# Sheet2.net
KiCad netlist of a schematic drawn in Altium Designer
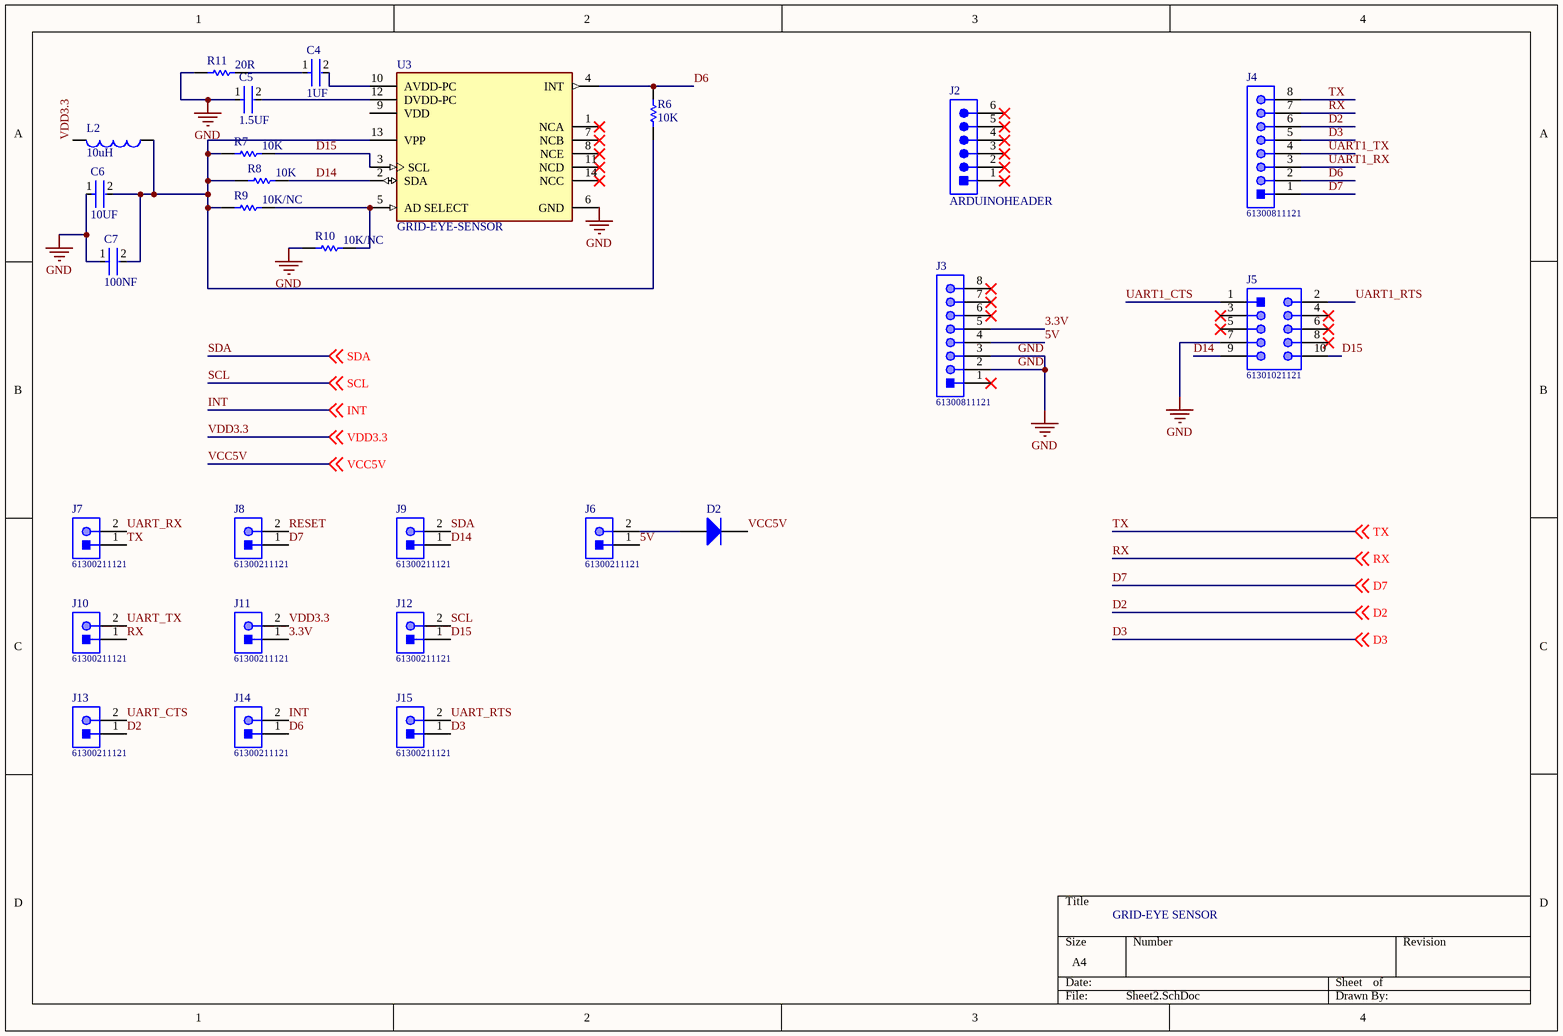
[diagram p0: Sheet2.SchDoc]

(export (version "E")
  (design (tool "Eeschema 10.0.6"))
  (components
    (comp (ref "C4")
      (value "1UF")
      (footprint "FP-C0805C-DN-MFG")
      (description "CAP CER 0.1UF 50V X7R 0805")
      (fields
        (field (name "MANUFACTURER PART NUMBER") "C0805C104K5RACTU")
        (field (name "MANUFACTURER") "KEMET")
      )
      (libsource (lib "Altium Content Vault") (part "b4654b650e69147ec39a6b967a45e02"))
    )
    (comp (ref "C5")
      (value "1.5UF")
      (footprint "FP-C0805C-DN-MFG")
      (description "CAP CER 0.1UF 50V X7R 0805")
      (fields
        (field (name "MANUFACTURER PART NUMBER") "C0805C104K5RACTU")
        (field (name "MANUFACTURER") "KEMET")
      )
      (libsource (lib "Altium Content Vault") (part "b4654b650e69147ec39a6b967a45e02"))
    )
    (comp (ref "C6")
      (value "10UF")
      (footprint "FP-C0805C-DN-MFG")
      (description "CAP CER 0.1UF 50V X7R 0805")
      (fields
        (field (name "MANUFACTURER PART NUMBER") "C0805C104K5RACTU")
        (field (name "MANUFACTURER") "KEMET")
      )
      (libsource (lib "Altium Content Vault") (part "b4654b650e69147ec39a6b967a45e02"))
    )
    (comp (ref "C7")
      (value "100NF")
      (footprint "FP-C0805C-DN-MFG")
      (description "CAP CER 0.1UF 50V X7R 0805")
      (fields
        (field (name "MANUFACTURER PART NUMBER") "C0805C104K5RACTU")
        (field (name "MANUFACTURER") "KEMET")
      )
      (libsource (lib "Altium Content Vault") (part "b4654b650e69147ec39a6b967a45e02"))
    )
    (comp (ref "D2")
      (value "1N4148W-7-F")
      (footprint "DIOD-SOD123-2_V")
      (description "Fast Switching Diode, 100 V, 0.15 A, -65 to 150 degC, 2-Pin?SOD123, RoHS, Tape and Reel")
      (fields (field (name "MANUFACTURER") "DiodesIncorporated"))
      (libsource (lib "Altium Content Vault") (part "D-AK-2"))
    )
    (comp (ref "J2")
      (value "ARDUINOHEADER")
      (footprint "TECO-640456-6_V")
      (fields (field (name "MANUFACTURER") "TE Connectivity"))
      (libsource (lib "Altium Content Vault") (part "CN-1P-M-R6"))
    )
    (comp (ref "J3")
      (value "61300811121")
      (footprint "61300811121")
      (description "THT Vertical Pin Header WR-PHD, Pitch 2.54 mm, Single Row, 8 pins")
      (fields (field (name "MANUFACTURER") "Wurth Elektronik") (field (name "PUBLISHER") "WurthElektronik"))
      (libsource (lib "Altium Content Vault") (part "WE-CN-1P-M-R8"))
    )
    (comp (ref "J4")
      (value "61300811121")
      (footprint "61300811121")
      (description "THT Vertical Pin Header WR-PHD, Pitch 2.54 mm, Single Row, 8 pins")
      (fields (field (name "MANUFACTURER") "Wurth Elektronik") (field (name "PUBLISHER") "WurthElektronik"))
      (libsource (lib "Altium Content Vault") (part "WE-CN-1P-M-R8"))
    )
    (comp (ref "J5")
      (value "61301021121")
      (footprint "61301021121")
      (description "THT Vertical Pin Header WR-PHD, Pitch 2.54 mm, Dual Row, 10 pins")
      (fields (field (name "MANUFACTURER") "Wurth Elektronik") (field (name "PUBLISHER") "WurthElektronik"))
      (libsource (lib "Altium Content Vault") (part "WE-CN-2P-M-R10"))
    )
    (comp (ref "J6")
      (value "61300211121")
      (footprint "61300211121")
      (description "THT Vertical Pin Header WR-PHD, Pitch 2.54 mm, Single Row, 2 pins")
      (fields (field (name "MANUFACTURER") "Wurth Elektronik") (field (name "PUBLISHER") "WurthElektronik"))
      (libsource (lib "Altium Content Vault") (part "WE-CN-1P-M-R2"))
    )
    (comp (ref "J7")
      (value "61300211121")
      (footprint "61300211121")
      (description "THT Vertical Pin Header WR-PHD, Pitch 2.54 mm, Single Row, 2 pins")
      (fields (field (name "MANUFACTURER") "Wurth Elektronik") (field (name "PUBLISHER") "WurthElektronik"))
      (libsource (lib "Altium Content Vault") (part "WE-CN-1P-M-R2"))
    )
    (comp (ref "J8")
      (value "61300211121")
      (footprint "61300211121")
      (description "THT Vertical Pin Header WR-PHD, Pitch 2.54 mm, Single Row, 2 pins")
      (fields (field (name "MANUFACTURER") "Wurth Elektronik") (field (name "PUBLISHER") "WurthElektronik"))
      (libsource (lib "Altium Content Vault") (part "WE-CN-1P-M-R2"))
    )
    (comp (ref "J9")
      (value "61300211121")
      (footprint "61300211121")
      (description "THT Vertical Pin Header WR-PHD, Pitch 2.54 mm, Single Row, 2 pins")
      (fields (field (name "MANUFACTURER") "Wurth Elektronik") (field (name "PUBLISHER") "WurthElektronik"))
      (libsource (lib "Altium Content Vault") (part "WE-CN-1P-M-R2"))
    )
    (comp (ref "J10")
      (value "61300211121")
      (footprint "61300211121")
      (description "THT Vertical Pin Header WR-PHD, Pitch 2.54 mm, Single Row, 2 pins")
      (fields (field (name "MANUFACTURER") "Wurth Elektronik") (field (name "PUBLISHER") "WurthElektronik"))
      (libsource (lib "Altium Content Vault") (part "WE-CN-1P-M-R2"))
    )
    (comp (ref "J11")
      (value "61300211121")
      (footprint "61300211121")
      (description "THT Vertical Pin Header WR-PHD, Pitch 2.54 mm, Single Row, 2 pins")
      (fields (field (name "MANUFACTURER") "Wurth Elektronik") (field (name "PUBLISHER") "WurthElektronik"))
      (libsource (lib "Altium Content Vault") (part "WE-CN-1P-M-R2"))
    )
    (comp (ref "J12")
      (value "61300211121")
      (footprint "61300211121")
      (description "THT Vertical Pin Header WR-PHD, Pitch 2.54 mm, Single Row, 2 pins")
      (fields (field (name "MANUFACTURER") "Wurth Elektronik") (field (name "PUBLISHER") "WurthElektronik"))
      (libsource (lib "Altium Content Vault") (part "WE-CN-1P-M-R2"))
    )
    (comp (ref "J13")
      (value "61300211121")
      (footprint "61300211121")
      (description "THT Vertical Pin Header WR-PHD, Pitch 2.54 mm, Single Row, 2 pins")
      (fields (field (name "MANUFACTURER") "Wurth Elektronik") (field (name "PUBLISHER") "WurthElektronik"))
      (libsource (lib "Altium Content Vault") (part "WE-CN-1P-M-R2"))
    )
    (comp (ref "J14")
      (value "61300211121")
      (footprint "61300211121")
      (description "THT Vertical Pin Header WR-PHD, Pitch 2.54 mm, Single Row, 2 pins")
      (fields (field (name "MANUFACTURER") "Wurth Elektronik") (field (name "PUBLISHER") "WurthElektronik"))
      (libsource (lib "Altium Content Vault") (part "WE-CN-1P-M-R2"))
    )
    (comp (ref "J15")
      (value "61300211121")
      (footprint "61300211121")
      (description "THT Vertical Pin Header WR-PHD, Pitch 2.54 mm, Single Row, 2 pins")
      (fields (field (name "MANUFACTURER") "Wurth Elektronik") (field (name "PUBLISHER") "WurthElektronik"))
      (libsource (lib "Altium Content Vault") (part "WE-CN-1P-M-R2"))
    )
    (comp (ref "L2")
      (value "10uH")
      (footprint "0402-A")
      (description "Inductor")
      (fields (field (name "PUBLISHER") "Altium Limited"))
      (libsource (lib "Miscellaneous Devices") (part "Inductor"))
    )
    (comp (ref "R6")
      (value "10K")
      (footprint "RESC1005X40X25NL05T10")
      (fields (field (name "MANUFACTURER") "Yageo / Phycomp") (field (name "PART NUMBER") "RC0402JR-070RL"))
      (libsource (lib "Altium Content Vault") (part "RES"))
    )
    (comp (ref "R7")
      (value "10K")
      (footprint "RESC1005X40X25NL05T10")
      (fields (field (name "MANUFACTURER") "Yageo / Phycomp") (field (name "PART NUMBER") "RC0402JR-070RL"))
      (libsource (lib "Altium Content Vault") (part "RES"))
    )
    (comp (ref "R8")
      (value "10K")
      (footprint "RESC1005X40X25NL05T10")
      (fields (field (name "MANUFACTURER") "Yageo / Phycomp") (field (name "PART NUMBER") "RC0402JR-070RL"))
      (libsource (lib "Altium Content Vault") (part "RES"))
    )
    (comp (ref "R9")
      (value "10K/NC")
      (footprint "RESC1005X40X25NL05T10")
      (fields (field (name "MANUFACTURER") "Yageo / Phycomp") (field (name "PART NUMBER") "RC0402JR-070RL"))
      (libsource (lib "Altium Content Vault") (part "RES"))
    )
    (comp (ref "R10")
      (value "10K/NC")
      (footprint "RESC1005X40X25NL05T10")
      (fields (field (name "MANUFACTURER") "Yageo / Phycomp") (field (name "PART NUMBER") "RC0402JR-070RL"))
      (libsource (lib "Altium Content Vault") (part "RES"))
    )
    (comp (ref "R11")
      (value "20R")
      (footprint "RESC1005X40X25NL05T10")
      (fields (field (name "MANUFACTURER") "Yageo / Phycomp") (field (name "PART NUMBER") "RC0402JR-070RL"))
      (libsource (lib "Altium Content Vault") (part "RES"))
    )
    (comp (ref "U3")
      (value "GRID-EYE-SENSOR")
      (footprint "FP-AMG8834-MFG")
      (description "SENSOR DGTL 14SMD MODULE")
      (libsource (lib "Altium Content Vault") (part "ec442dd7c251b4f93a93aecae9a6d86"))
    )
  )
  (nets
    (net (code "1") (name "/3.3V") (class "Default")
      (node (ref "J11") (pin "1") (pinfunction "1_1") (pintype "passive"))
      (node (ref "J3") (pin "5") (pinfunction "5_5") (pintype "passive"))
    )
    (net (code "2") (name "/5V") (class "Default")
      (node (ref "J3") (pin "4") (pinfunction "4_4") (pintype "passive"))
      (node (ref "J6") (pin "1") (pinfunction "1_1") (pintype "passive"))
    )
    (net (code "3") (name "/D6") (class "Default")
      (node (ref "J14") (pin "1") (pinfunction "1_1") (pintype "passive"))
      (node (ref "J4") (pin "2") (pinfunction "2_2") (pintype "passive"))
      (node (ref "R6") (pin "2") (pinfunction "2_2") (pintype "passive"))
      (node (ref "U3") (pin "4") (pinfunction "INT_4") (pintype "output"))
    )
    (net (code "4") (name "/D14") (class "Default")
      (node (ref "J5") (pin "9") (pinfunction "9_9") (pintype "passive"))
      (node (ref "J9") (pin "1") (pinfunction "1_1") (pintype "passive"))
      (node (ref "R8") (pin "2") (pinfunction "2_2") (pintype "passive"))
      (node (ref "U3") (pin "2") (pinfunction "SDA_2") (pintype "bidirectional"))
    )
    (net (code "5") (name "/D15") (class "Default")
      (node (ref "J12") (pin "1") (pinfunction "1_1") (pintype "passive"))
      (node (ref "J5") (pin "10") (pinfunction "10_10") (pintype "passive"))
      (node (ref "R7") (pin "2") (pinfunction "2_2") (pintype "passive"))
      (node (ref "U3") (pin "3") (pinfunction "SCL_3") (pintype "input"))
    )
    (net (code "6") (name "/RESET") (class "Default")
      (node (ref "J8") (pin "2") (pinfunction "2_2") (pintype "passive"))
    )
    (net (code "7") (name "/UART1_CTS") (class "Default")
      (node (ref "J5") (pin "1") (pinfunction "1_1") (pintype "passive"))
    )
    (net (code "8") (name "/UART1_RTS") (class "Default")
      (node (ref "J5") (pin "2") (pinfunction "2_2") (pintype "passive"))
    )
    (net (code "9") (name "/UART1_RX") (class "Default")
      (node (ref "J4") (pin "3") (pinfunction "3_3") (pintype "passive"))
    )
    (net (code "10") (name "/UART1_TX") (class "Default")
      (node (ref "J4") (pin "4") (pinfunction "4_4") (pintype "passive"))
    )
    (net (code "11") (name "/UART_CTS") (class "Default")
      (node (ref "J13") (pin "2") (pinfunction "2_2") (pintype "passive"))
    )
    (net (code "12") (name "/UART_RTS") (class "Default")
      (node (ref "J15") (pin "2") (pinfunction "2_2") (pintype "passive"))
    )
    (net (code "13") (name "/UART_RX") (class "Default")
      (node (ref "J7") (pin "2") (pinfunction "2_2") (pintype "passive"))
    )
    (net (code "14") (name "/UART_TX") (class "Default")
      (node (ref "J10") (pin "2") (pinfunction "2_2") (pintype "passive"))
    )
    (net (code "15") (name "D2") (class "Default")
      (node (ref "J13") (pin "1") (pinfunction "1_1") (pintype "passive"))
      (node (ref "J4") (pin "6") (pinfunction "6_6") (pintype "passive"))
    )
    (net (code "16") (name "D3") (class "Default")
      (node (ref "J15") (pin "1") (pinfunction "1_1") (pintype "passive"))
      (node (ref "J4") (pin "5") (pinfunction "5_5") (pintype "passive"))
    )
    (net (code "17") (name "D7") (class "Default")
      (node (ref "J4") (pin "1") (pinfunction "1_1") (pintype "passive"))
      (node (ref "J8") (pin "1") (pinfunction "1_1") (pintype "passive"))
    )
    (net (code "18") (name "GND") (class "Default")
      (node (ref "C5") (pin "1") (pinfunction "1_1") (pintype "passive"))
      (node (ref "C6") (pin "1") (pinfunction "1_1") (pintype "passive"))
      (node (ref "C7") (pin "1") (pinfunction "1_1") (pintype "passive"))
      (node (ref "J3") (pin "2") (pinfunction "2_2") (pintype "passive"))
      (node (ref "J3") (pin "3") (pinfunction "3_3") (pintype "passive"))
      (node (ref "J5") (pin "7") (pinfunction "7_7") (pintype "passive"))
      (node (ref "R10") (pin "1") (pinfunction "1_1") (pintype "passive"))
      (node (ref "R11") (pin "1") (pinfunction "1_1") (pintype "passive"))
      (node (ref "U3") (pin "6") (pinfunction "GND_6") (pintype "power_in"))
    )
    (net (code "19") (name "INT") (class "Default")
      (node (ref "J14") (pin "2") (pinfunction "2_2") (pintype "passive"))
    )
    (net (code "20") (name "Net-(C4-Pad1)") (class "Default")
      (node (ref "C4") (pin "1") (pinfunction "1_1") (pintype "passive"))
      (node (ref "R11") (pin "2") (pinfunction "2_2") (pintype "passive"))
    )
    (net (code "21") (name "Net-(D2-A)") (class "Default")
      (node (ref "D2") (pin "1") (pinfunction "A_1") (pintype "passive"))
      (node (ref "J6") (pin "2") (pinfunction "2_2") (pintype "passive"))
    )
    (net (code "22") (name "Net-(U3-AD_SELECT)") (class "Default")
      (node (ref "R10") (pin "2") (pinfunction "2_2") (pintype "passive"))
      (node (ref "R9") (pin "2") (pinfunction "2_2") (pintype "passive"))
      (node (ref "U3") (pin "5") (pinfunction "AD_SELECT_5") (pintype "input"))
    )
    (net (code "23") (name "Net-(U3-AVDD-PC)") (class "Default")
      (node (ref "C4") (pin "2") (pinfunction "2_2") (pintype "passive"))
      (node (ref "U3") (pin "10") (pinfunction "AVDD-PC_10") (pintype "power_in"))
    )
    (net (code "24") (name "Net-(U3-DVDD-PC)") (class "Default")
      (node (ref "C5") (pin "2") (pinfunction "2_2") (pintype "passive"))
      (node (ref "U3") (pin "12") (pinfunction "DVDD-PC_12") (pintype "power_in"))
    )
    (net (code "25") (name "Net-(U3-VPP)") (class "Default")
      (node (ref "C6") (pin "2") (pinfunction "2_2") (pintype "passive"))
      (node (ref "C7") (pin "2") (pinfunction "2_2") (pintype "passive"))
      (node (ref "L2") (pin "1") (pinfunction "1_1") (pintype "passive"))
      (node (ref "R6") (pin "1") (pinfunction "1_1") (pintype "passive"))
      (node (ref "R7") (pin "1") (pinfunction "1_1") (pintype "passive"))
      (node (ref "R8") (pin "1") (pinfunction "1_1") (pintype "passive"))
      (node (ref "R9") (pin "1") (pinfunction "1_1") (pintype "passive"))
      (node (ref "U3") (pin "13") (pinfunction "VPP_13") (pintype "power_in"))
    )
    (net (code "26") (name "RX") (class "Default")
      (node (ref "J10") (pin "1") (pinfunction "1_1") (pintype "passive"))
      (node (ref "J4") (pin "7") (pinfunction "7_7") (pintype "passive"))
    )
    (net (code "27") (name "SCL") (class "Default")
      (node (ref "J12") (pin "2") (pinfunction "2_2") (pintype "passive"))
    )
    (net (code "28") (name "SDA") (class "Default")
      (node (ref "J9") (pin "2") (pinfunction "2_2") (pintype "passive"))
    )
    (net (code "29") (name "TX") (class "Default")
      (node (ref "J4") (pin "8") (pinfunction "8_8") (pintype "passive"))
      (node (ref "J7") (pin "1") (pinfunction "1_1") (pintype "passive"))
    )
    (net (code "30") (name "VCC5V") (class "Default")
      (node (ref "D2") (pin "2") (pinfunction "K_2") (pintype "passive"))
    )
    (net (code "31") (name "VDD3.3") (class "Default")
      (node (ref "J11") (pin "2") (pinfunction "2_2") (pintype "passive"))
      (node (ref "L2") (pin "2") (pinfunction "2_2") (pintype "passive"))
    )
    (net (code "32") (name "unconnected-(J2-Pad1)") (class "Default")
      (node (ref "J2") (pin "1") (pinfunction "1_1") (pintype "passive+no_connect"))
    )
    (net (code "33") (name "unconnected-(J2-Pad2)") (class "Default")
      (node (ref "J2") (pin "2") (pinfunction "2_2") (pintype "passive+no_connect"))
    )
    (net (code "34") (name "unconnected-(J2-Pad3)") (class "Default")
      (node (ref "J2") (pin "3") (pinfunction "3_3") (pintype "passive+no_connect"))
    )
    (net (code "35") (name "unconnected-(J2-Pad4)") (class "Default")
      (node (ref "J2") (pin "4") (pinfunction "4_4") (pintype "passive+no_connect"))
    )
    (net (code "36") (name "unconnected-(J2-Pad5)") (class "Default")
      (node (ref "J2") (pin "5") (pinfunction "5_5") (pintype "passive+no_connect"))
    )
    (net (code "37") (name "unconnected-(J2-Pad6)") (class "Default")
      (node (ref "J2") (pin "6") (pinfunction "6_6") (pintype "passive+no_connect"))
    )
    (net (code "38") (name "unconnected-(J3-Pad1)") (class "Default")
      (node (ref "J3") (pin "1") (pinfunction "1_1") (pintype "passive+no_connect"))
    )
    (net (code "39") (name "unconnected-(J3-Pad6)") (class "Default")
      (node (ref "J3") (pin "6") (pinfunction "6_6") (pintype "passive+no_connect"))
    )
    (net (code "40") (name "unconnected-(J3-Pad7)") (class "Default")
      (node (ref "J3") (pin "7") (pinfunction "7_7") (pintype "passive+no_connect"))
    )
    (net (code "41") (name "unconnected-(J3-Pad8)") (class "Default")
      (node (ref "J3") (pin "8") (pinfunction "8_8") (pintype "passive+no_connect"))
    )
    (net (code "42") (name "unconnected-(J5-Pad3)") (class "Default")
      (node (ref "J5") (pin "3") (pinfunction "3_3") (pintype "passive+no_connect"))
    )
    (net (code "43") (name "unconnected-(J5-Pad4)") (class "Default")
      (node (ref "J5") (pin "4") (pinfunction "4_4") (pintype "passive+no_connect"))
    )
    (net (code "44") (name "unconnected-(J5-Pad5)") (class "Default")
      (node (ref "J5") (pin "5") (pinfunction "5_5") (pintype "passive+no_connect"))
    )
    (net (code "45") (name "unconnected-(J5-Pad6)") (class "Default")
      (node (ref "J5") (pin "6") (pinfunction "6_6") (pintype "passive+no_connect"))
    )
    (net (code "46") (name "unconnected-(J5-Pad8)") (class "Default")
      (node (ref "J5") (pin "8") (pinfunction "8_8") (pintype "passive+no_connect"))
    )
    (net (code "47") (name "unconnected-(U3-NCA-Pad1)") (class "Default")
      (node (ref "U3") (pin "1") (pinfunction "NCA_1") (pintype "passive+no_connect"))
    )
    (net (code "48") (name "unconnected-(U3-NCB-Pad7)") (class "Default")
      (node (ref "U3") (pin "7") (pinfunction "NCB_7") (pintype "passive+no_connect"))
    )
    (net (code "49") (name "unconnected-(U3-NCC-Pad14)") (class "Default")
      (node (ref "U3") (pin "14") (pinfunction "NCC_14") (pintype "passive+no_connect"))
    )
    (net (code "50") (name "unconnected-(U3-NCD-Pad11)") (class "Default")
      (node (ref "U3") (pin "11") (pinfunction "NCD_11") (pintype "passive+no_connect"))
    )
    (net (code "51") (name "unconnected-(U3-NCE-Pad8)") (class "Default")
      (node (ref "U3") (pin "8") (pinfunction "NCE_8") (pintype "passive+no_connect"))
    )
    (net (code "52") (name "unconnected-(U3-VDD-Pad9)") (class "Default")
      (node (ref "U3") (pin "9") (pinfunction "VDD_9") (pintype "power_in"))
    )
  )
)
